# L9963E.net
KiCad netlist of a schematic drawn in Altium Designer
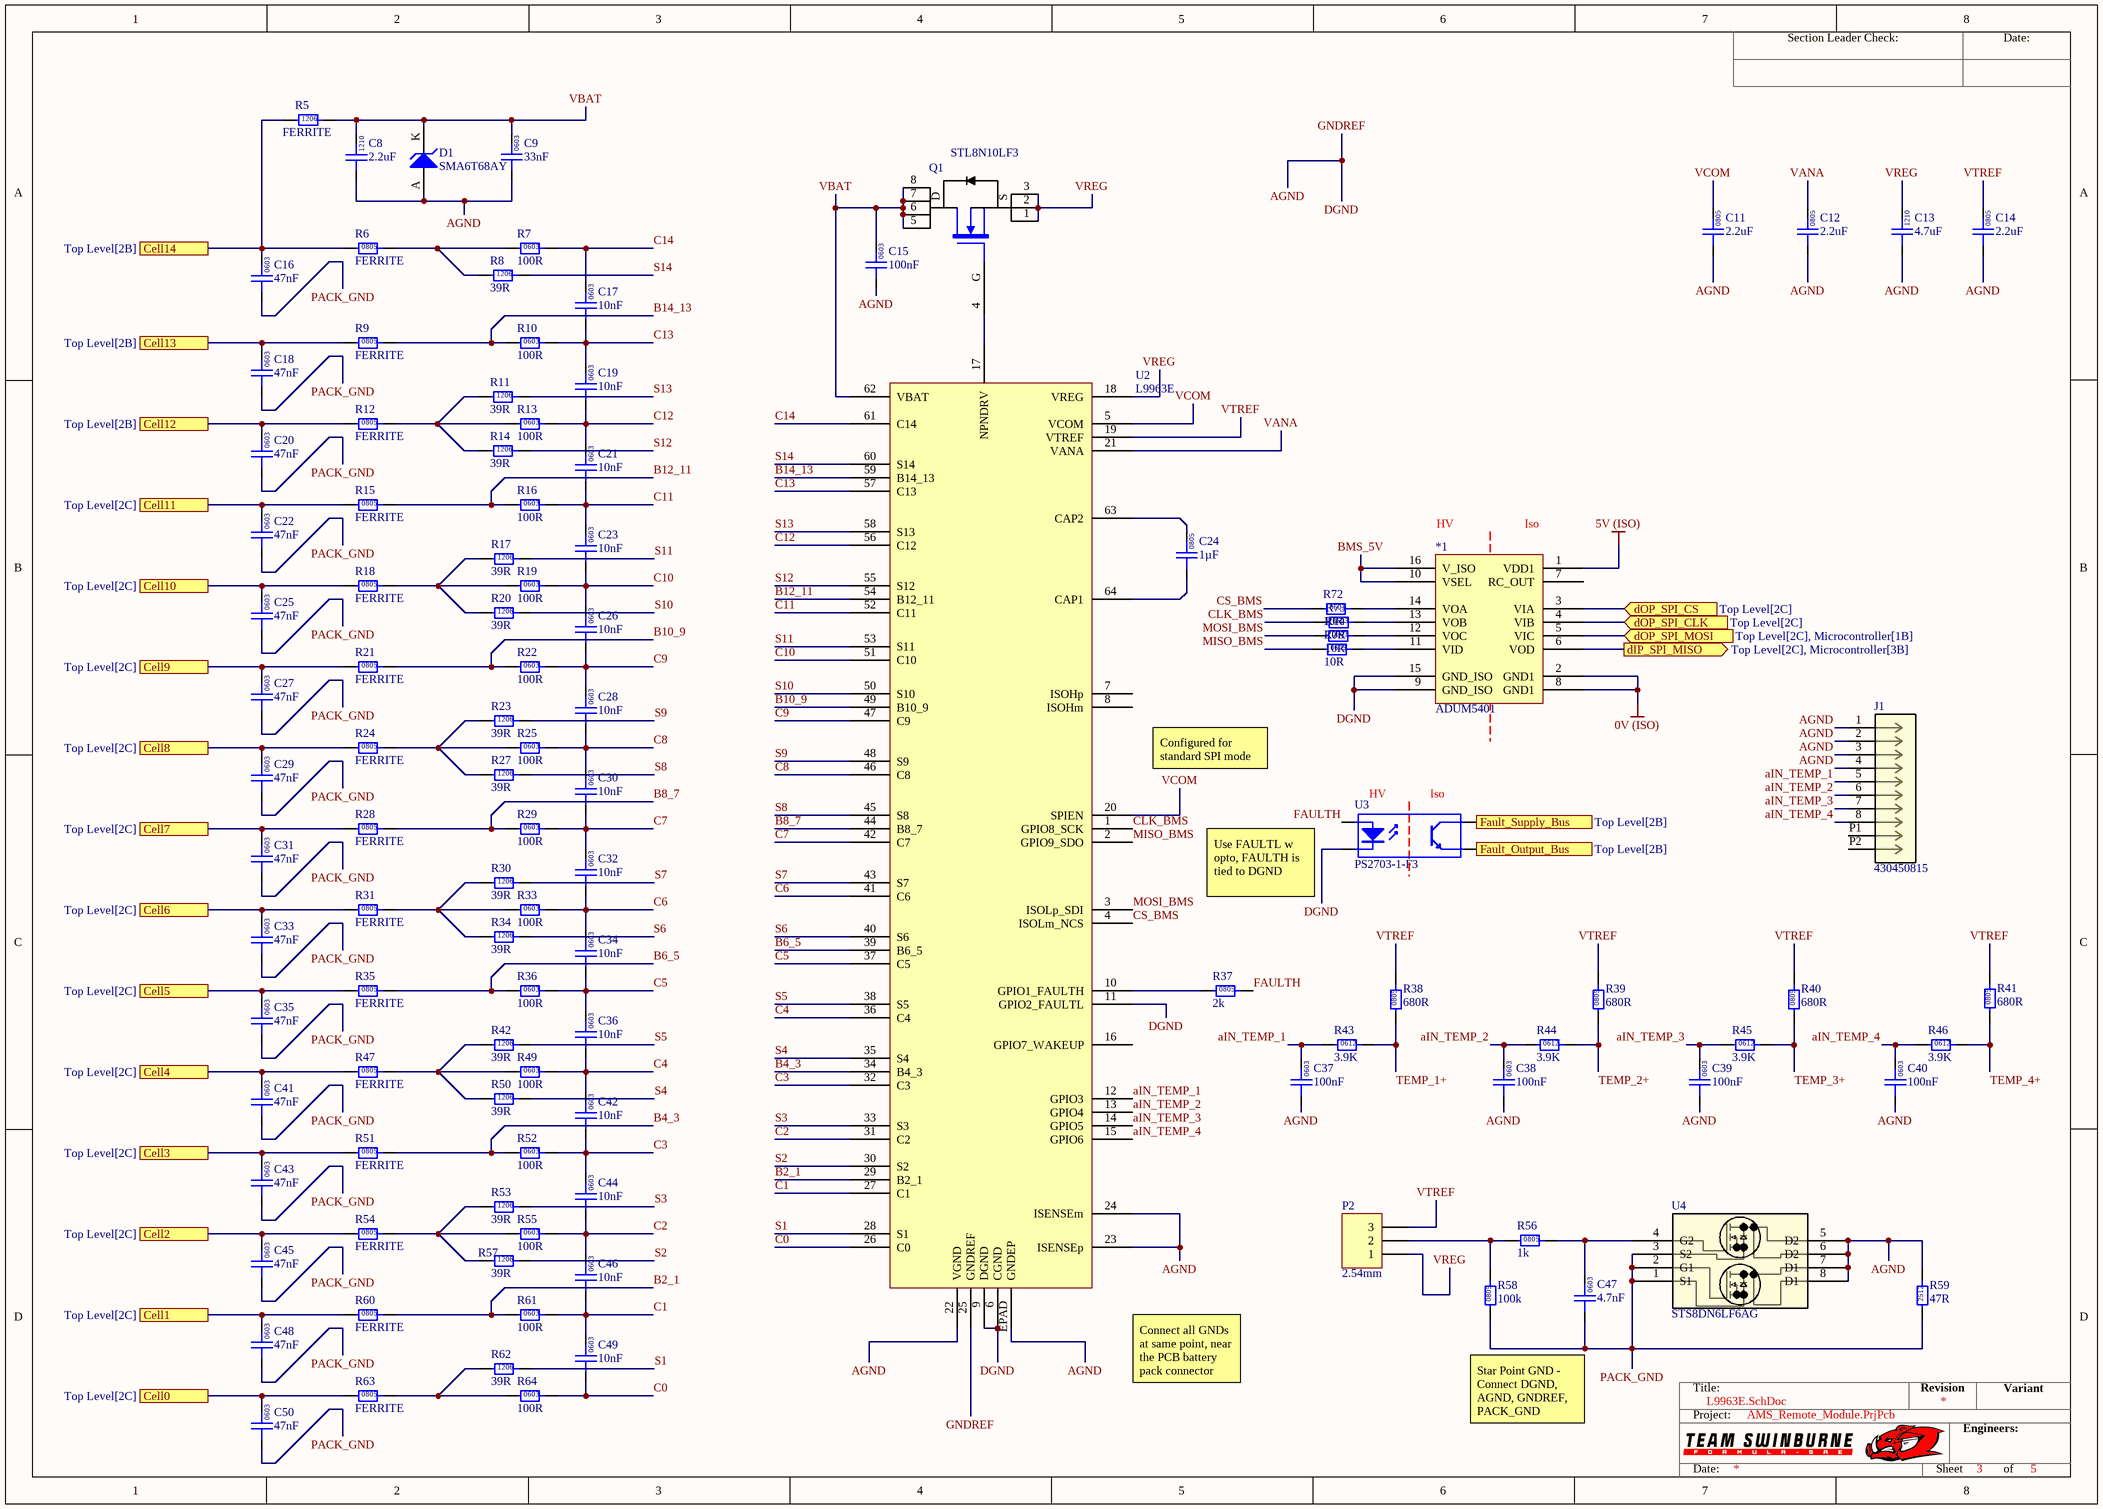
[diagram p0: L9963E.SchDoc]

(export (version "E")
  (design (tool "Eeschema 10.0.6"))
  (components
    (comp (ref "*1")
      (value "ADUM5401")
      (footprint "AD 16-SOIC")
      (description "Quad Channel 2.5kV Digital Isolator with isoPower")
      (fields (field (name "MANUFACTURER") "Analogue Devices"))
      (libsource (lib "ts_standard_library") (part "ADUM5401"))
    )
    (comp (ref "C8")
      (value "2.2uF")
      (footprint "1210")
      (fields
        (field (name "PART NUMBER") "CL32B225KCJSNNE")
        (field (name "MANUFACTURER") "Samsung Electro-Mechanics")
        (field (name "TOLERANCE") "±10%")
      )
      (libsource (lib "ts_standard_library") (part "Capacitor 1210"))
    )
    (comp (ref "C9")
      (value "33nF")
      (footprint "0603")
      (fields
        (field (name "PART NUMBER") "CL10B333KC8WPNC")
        (field (name "MANUFACTURER") "Samsung Electro-Mechanics")
        (field (name "TOLERANCE") "±10%")
      )
      (libsource (lib "ts_standard_library") (part "Capacitor 0603"))
    )
    (comp (ref "C11")
      (value "2.2uF")
      (footprint "0805")
      (fields
        (field (name "PART NUMBER") "GRM21BR71E225KE11L")
        (field (name "MANUFACTURER") "Murata Electronics")
        (field (name "TOLERANCE") "±10%")
      )
      (libsource (lib "ts_standard_library") (part "Capacitor 0805"))
    )
    (comp (ref "C12")
      (value "2.2uF")
      (footprint "0805")
      (fields
        (field (name "PART NUMBER") "GRM21BR71E225KE11L")
        (field (name "MANUFACTURER") "Murata Electronics")
        (field (name "TOLERANCE") "±10%")
      )
      (libsource (lib "ts_standard_library") (part "Capacitor 0805"))
    )
    (comp (ref "C13")
      (value "4.7uF")
      (footprint "1210")
      (fields
        (field (name "PART NUMBER") "C1210X475K101T")
        (field (name "MANUFACTURER") "Holy Stone Enterprise Co., Ltd.")
        (field (name "TOLERANCE") "±10%")
      )
      (libsource (lib "ts_standard_library") (part "Capacitor 1210"))
    )
    (comp (ref "C14")
      (value "2.2uF")
      (footprint "0805")
      (fields
        (field (name "PART NUMBER") "GRM21BR71E225KE11L")
        (field (name "MANUFACTURER") "Murata Electronics")
        (field (name "TOLERANCE") "±10%")
      )
      (libsource (lib "ts_standard_library") (part "Capacitor 0805"))
    )
    (comp (ref "C15")
      (value "100nF")
      (footprint "0603")
      (fields
        (field (name "PART NUMBER") "CL10B104KC8NNNC")
        (field (name "MANUFACTURER") "Samsung Electro-Mechanics")
        (field (name "TOLERANCE") "±10%")
      )
      (libsource (lib "ts_standard_library") (part "Capacitor 0603"))
    )
    (comp (ref "C16")
      (value "47nF")
      (footprint "0603")
      (fields
        (field (name "PART NUMBER") "GCJ188R92A473KA01D")
        (field (name "MANUFACTURER") "Murata Electronics")
        (field (name "TOLERANCE") "±10%")
      )
      (libsource (lib "ts_standard_library") (part "Capacitor 0603"))
    )
    (comp (ref "C17")
      (value "10nF")
      (footprint "0603")
      (fields
        (field (name "PART NUMBER") "GCM188L81H103KA03D")
        (field (name "MANUFACTURER") "muRata")
        (field (name "TOLERANCE") "±10%")
      )
      (libsource (lib "ts_standard_library") (part "Capacitor 0603"))
    )
    (comp (ref "C18")
      (value "47nF")
      (footprint "0603")
      (fields
        (field (name "PART NUMBER") "GCJ188R92A473KA01D")
        (field (name "MANUFACTURER") "Murata Electronics")
        (field (name "TOLERANCE") "±10%")
      )
      (libsource (lib "ts_standard_library") (part "Capacitor 0603"))
    )
    (comp (ref "C19")
      (value "10nF")
      (footprint "0603")
      (fields
        (field (name "PART NUMBER") "GCM188L81H103KA03D")
        (field (name "MANUFACTURER") "muRata")
        (field (name "TOLERANCE") "±10%")
      )
      (libsource (lib "ts_standard_library") (part "Capacitor 0603"))
    )
    (comp (ref "C20")
      (value "47nF")
      (footprint "0603")
      (fields
        (field (name "PART NUMBER") "GCJ188R92A473KA01D")
        (field (name "MANUFACTURER") "Murata Electronics")
        (field (name "TOLERANCE") "±10%")
      )
      (libsource (lib "ts_standard_library") (part "Capacitor 0603"))
    )
    (comp (ref "C21")
      (value "10nF")
      (footprint "0603")
      (fields
        (field (name "PART NUMBER") "GCM188L81H103KA03D")
        (field (name "MANUFACTURER") "muRata")
        (field (name "TOLERANCE") "±10%")
      )
      (libsource (lib "ts_standard_library") (part "Capacitor 0603"))
    )
    (comp (ref "C22")
      (value "47nF")
      (footprint "0603")
      (fields
        (field (name "PART NUMBER") "GCJ188R92A473KA01D")
        (field (name "MANUFACTURER") "Murata Electronics")
        (field (name "TOLERANCE") "±10%")
      )
      (libsource (lib "ts_standard_library") (part "Capacitor 0603"))
    )
    (comp (ref "C23")
      (value "10nF")
      (footprint "0603")
      (fields
        (field (name "PART NUMBER") "GCM188L81H103KA03D")
        (field (name "MANUFACTURER") "muRata")
        (field (name "TOLERANCE") "±10%")
      )
      (libsource (lib "ts_standard_library") (part "Capacitor 0603"))
    )
    (comp (ref "C24")
      (value "1µF")
      (footprint "0805")
      (fields
        (field (name "PART NUMBER") "GCM21BR71H105KA03L")
        (field (name "MANUFACTURER") "muRata")
        (field (name "TOLERANCE") "±10%")
      )
      (libsource (lib "ts_standard_library") (part "Capacitor 0805"))
    )
    (comp (ref "C25")
      (value "47nF")
      (footprint "0603")
      (fields
        (field (name "PART NUMBER") "GCJ188R92A473KA01D")
        (field (name "MANUFACTURER") "Murata Electronics")
        (field (name "TOLERANCE") "±10%")
      )
      (libsource (lib "ts_standard_library") (part "Capacitor 0603"))
    )
    (comp (ref "C26")
      (value "10nF")
      (footprint "0603")
      (fields
        (field (name "PART NUMBER") "GCM188L81H103KA03D")
        (field (name "MANUFACTURER") "muRata")
        (field (name "TOLERANCE") "±10%")
      )
      (libsource (lib "ts_standard_library") (part "Capacitor 0603"))
    )
    (comp (ref "C27")
      (value "47nF")
      (footprint "0603")
      (fields
        (field (name "PART NUMBER") "GCJ188R92A473KA01D")
        (field (name "MANUFACTURER") "Murata Electronics")
        (field (name "TOLERANCE") "±10%")
      )
      (libsource (lib "ts_standard_library") (part "Capacitor 0603"))
    )
    (comp (ref "C28")
      (value "10nF")
      (footprint "0603")
      (fields
        (field (name "PART NUMBER") "GCM188L81H103KA03D")
        (field (name "MANUFACTURER") "muRata")
        (field (name "TOLERANCE") "±10%")
      )
      (libsource (lib "ts_standard_library") (part "Capacitor 0603"))
    )
    (comp (ref "C29")
      (value "47nF")
      (footprint "0603")
      (fields
        (field (name "PART NUMBER") "GCJ188R92A473KA01D")
        (field (name "MANUFACTURER") "Murata Electronics")
        (field (name "TOLERANCE") "±10%")
      )
      (libsource (lib "ts_standard_library") (part "Capacitor 0603"))
    )
    (comp (ref "C30")
      (value "10nF")
      (footprint "0603")
      (fields
        (field (name "PART NUMBER") "GCM188L81H103KA03D")
        (field (name "MANUFACTURER") "muRata")
        (field (name "TOLERANCE") "±10%")
      )
      (libsource (lib "ts_standard_library") (part "Capacitor 0603"))
    )
    (comp (ref "C31")
      (value "47nF")
      (footprint "0603")
      (fields
        (field (name "PART NUMBER") "GCJ188R92A473KA01D")
        (field (name "MANUFACTURER") "Murata Electronics")
        (field (name "TOLERANCE") "±10%")
      )
      (libsource (lib "ts_standard_library") (part "Capacitor 0603"))
    )
    (comp (ref "C32")
      (value "10nF")
      (footprint "0603")
      (fields
        (field (name "PART NUMBER") "GCM188L81H103KA03D")
        (field (name "MANUFACTURER") "muRata")
        (field (name "TOLERANCE") "±10%")
      )
      (libsource (lib "ts_standard_library") (part "Capacitor 0603"))
    )
    (comp (ref "C33")
      (value "47nF")
      (footprint "0603")
      (fields
        (field (name "PART NUMBER") "GCJ188R92A473KA01D")
        (field (name "MANUFACTURER") "Murata Electronics")
        (field (name "TOLERANCE") "±10%")
      )
      (libsource (lib "ts_standard_library") (part "Capacitor 0603"))
    )
    (comp (ref "C34")
      (value "10nF")
      (footprint "0603")
      (fields
        (field (name "PART NUMBER") "GCM188L81H103KA03D")
        (field (name "MANUFACTURER") "muRata")
        (field (name "TOLERANCE") "±10%")
      )
      (libsource (lib "ts_standard_library") (part "Capacitor 0603"))
    )
    (comp (ref "C35")
      (value "47nF")
      (footprint "0603")
      (fields
        (field (name "PART NUMBER") "GCJ188R92A473KA01D")
        (field (name "MANUFACTURER") "Murata Electronics")
        (field (name "TOLERANCE") "±10%")
      )
      (libsource (lib "ts_standard_library") (part "Capacitor 0603"))
    )
    (comp (ref "C36")
      (value "10nF")
      (footprint "0603")
      (fields
        (field (name "PART NUMBER") "GCM188L81H103KA03D")
        (field (name "MANUFACTURER") "muRata")
        (field (name "TOLERANCE") "±10%")
      )
      (libsource (lib "ts_standard_library") (part "Capacitor 0603"))
    )
    (comp (ref "C37")
      (value "100nF")
      (footprint "0603")
      (fields
        (field (name "PART NUMBER") "CL10B104KC8NNNC")
        (field (name "MANUFACTURER") "Samsung Electro-Mechanics")
        (field (name "TOLERANCE") "±10%")
      )
      (libsource (lib "ts_standard_library") (part "Capacitor 0603"))
    )
    (comp (ref "C38")
      (value "100nF")
      (footprint "0603")
      (fields
        (field (name "PART NUMBER") "CL10B104KC8NNNC")
        (field (name "MANUFACTURER") "Samsung Electro-Mechanics")
        (field (name "TOLERANCE") "±10%")
      )
      (libsource (lib "ts_standard_library") (part "Capacitor 0603"))
    )
    (comp (ref "C39")
      (value "100nF")
      (footprint "0603")
      (fields
        (field (name "PART NUMBER") "CL10B104KC8NNNC")
        (field (name "MANUFACTURER") "Samsung Electro-Mechanics")
        (field (name "TOLERANCE") "±10%")
      )
      (libsource (lib "ts_standard_library") (part "Capacitor 0603"))
    )
    (comp (ref "C40")
      (value "100nF")
      (footprint "0603")
      (fields
        (field (name "PART NUMBER") "CL10B104KC8NNNC")
        (field (name "MANUFACTURER") "Samsung Electro-Mechanics")
        (field (name "TOLERANCE") "±10%")
      )
      (libsource (lib "ts_standard_library") (part "Capacitor 0603"))
    )
    (comp (ref "C41")
      (value "47nF")
      (footprint "0603")
      (fields
        (field (name "PART NUMBER") "GCJ188R92A473KA01D")
        (field (name "MANUFACTURER") "Murata Electronics")
        (field (name "TOLERANCE") "±10%")
      )
      (libsource (lib "ts_standard_library") (part "Capacitor 0603"))
    )
    (comp (ref "C42")
      (value "10nF")
      (footprint "0603")
      (fields
        (field (name "PART NUMBER") "GCM188L81H103KA03D")
        (field (name "MANUFACTURER") "muRata")
        (field (name "TOLERANCE") "±10%")
      )
      (libsource (lib "ts_standard_library") (part "Capacitor 0603"))
    )
    (comp (ref "C43")
      (value "47nF")
      (footprint "0603")
      (fields
        (field (name "PART NUMBER") "GCJ188R92A473KA01D")
        (field (name "MANUFACTURER") "Murata Electronics")
        (field (name "TOLERANCE") "±10%")
      )
      (libsource (lib "ts_standard_library") (part "Capacitor 0603"))
    )
    (comp (ref "C44")
      (value "10nF")
      (footprint "0603")
      (fields
        (field (name "PART NUMBER") "GCM188L81H103KA03D")
        (field (name "MANUFACTURER") "muRata")
        (field (name "TOLERANCE") "±10%")
      )
      (libsource (lib "ts_standard_library") (part "Capacitor 0603"))
    )
    (comp (ref "C45")
      (value "47nF")
      (footprint "0603")
      (fields
        (field (name "PART NUMBER") "GCJ188R92A473KA01D")
        (field (name "MANUFACTURER") "Murata Electronics")
        (field (name "TOLERANCE") "±10%")
      )
      (libsource (lib "ts_standard_library") (part "Capacitor 0603"))
    )
    (comp (ref "C46")
      (value "10nF")
      (footprint "0603")
      (fields
        (field (name "PART NUMBER") "GCM188L81H103KA03D")
        (field (name "MANUFACTURER") "muRata")
        (field (name "TOLERANCE") "±10%")
      )
      (libsource (lib "ts_standard_library") (part "Capacitor 0603"))
    )
    (comp (ref "C47")
      (value "4.7nF")
      (footprint "0603")
      (fields
        (field (name "PART NUMBER") "CGA3E2X7R2A472K080AA")
        (field (name "MANUFACTURER") "TDK Corporation")
        (field (name "TOLERANCE") "±10%")
      )
      (libsource (lib "ts_standard_library") (part "Capacitor 0603"))
    )
    (comp (ref "C48")
      (value "47nF")
      (footprint "0603")
      (fields
        (field (name "PART NUMBER") "GCJ188R92A473KA01D")
        (field (name "MANUFACTURER") "Murata Electronics")
        (field (name "TOLERANCE") "±10%")
      )
      (libsource (lib "ts_standard_library") (part "Capacitor 0603"))
    )
    (comp (ref "C49")
      (value "10nF")
      (footprint "0603")
      (fields
        (field (name "PART NUMBER") "GCM188L81H103KA03D")
        (field (name "MANUFACTURER") "muRata")
        (field (name "TOLERANCE") "±10%")
      )
      (libsource (lib "ts_standard_library") (part "Capacitor 0603"))
    )
    (comp (ref "C50")
      (value "47nF")
      (footprint "0603")
      (fields
        (field (name "PART NUMBER") "GCJ188R92A473KA01D")
        (field (name "MANUFACTURER") "Murata Electronics")
        (field (name "TOLERANCE") "±10%")
      )
      (libsource (lib "ts_standard_library") (part "Capacitor 0603"))
    )
    (comp (ref "D1")
      (value "SMA6T68AY")
      (footprint "ST SMB DIODE")
      (fields (field (name "MANUFACTURER") "STMicroelectronics"))
      (libsource (lib "ts_standard_library") (part "Zener Diode"))
    )
    (comp (ref "J1")
      (value "430450815")
      (footprint "430450815")
      (description "No Description Available")
      (fields (field (name "DIGIKEY PART NUMBER") "WM7067DKR-ND") (field (name "CONTACT") "Gold"))
      (libsource (lib "ts_standard_connectors") (part "430450815"))
    )
    (comp (ref "P2")
      (value "2.54mm")
      (footprint "TH 2.54mm Header 1x3")
      (fields (field (name "PART NUMBER") "TH 2.54mm Header 1x3") (field (name "CONTACT") "NA"))
      (libsource (lib "ts_standard_connectors") (part "Header 1x3"))
    )
    (comp (ref "Q1")
      (value "STL8N10LF3")
      (footprint "TRANS_STL60P4LLF6")
      (description "N-Channel 100 V 20A (Tc) 4.3W (Ta), 70W (Tc) Surface Mount PowerFlat™ (5x6)")
      (fields
        (field (name "MANUFACTURER") "STMicroelectronics")
        (field (name "DIGIKEY PART NUMBER") "497-13652-6-ND")
        (field (name "PUBLISHER") "Altium Limited")
      )
      (libsource (lib "ts_standard_library") (part "STL8N10LF3"))
    )
    (comp (ref "R5")
      (value "FERRITE")
      (footprint "1206")
      (fields
        (field (name "PART NUMBER") "BLM31KN102SH1L")
        (field (name "MANUFACTURER") "Murata Electronics")
        (field (name "DIGIKEY PART NUMBER") "490-16520-6-ND")
      )
      (libsource (lib "ts_standard_library") (part "Resistor 1206"))
    )
    (comp (ref "R6")
      (value "FERRITE")
      (footprint "0805")
      (fields (field (name "PART NUMBER") "MPZ2012S102ATD25") (field (name "MANUFACTURER") "TDK"))
      (libsource (lib "ts_standard_library") (part "Resistor 0805"))
    )
    (comp (ref "R7")
      (value "100R")
      (footprint "0603")
      (fields
        (field (name "PART NUMBER") "RC0603FR-0710RL")
        (field (name "MANUFACTURER") "YAGEO")
        (field (name "TOLERANCE") "0.01")
      )
      (libsource (lib "ts_standard_library") (part "Resistor 0603"))
    )
    (comp (ref "R8")
      (value "39R")
      (footprint "1206")
      (fields
        (field (name "PART NUMBER") "CRCW120639R0FKEAHP")
        (field (name "MANUFACTURER") "Vishay Dale")
        (field (name "TOLERANCE") "0.01")
      )
      (libsource (lib "ts_standard_library") (part "Resistor 1206"))
    )
    (comp (ref "R9")
      (value "FERRITE")
      (footprint "0805")
      (fields (field (name "PART NUMBER") "MPZ2012S102ATD25") (field (name "MANUFACTURER") "TDK"))
      (libsource (lib "ts_standard_library") (part "Resistor 0805"))
    )
    (comp (ref "R10")
      (value "100R")
      (footprint "0603")
      (fields
        (field (name "PART NUMBER") "RC0603FR-0710RL")
        (field (name "MANUFACTURER") "YAGEO")
        (field (name "TOLERANCE") "0.01")
      )
      (libsource (lib "ts_standard_library") (part "Resistor 0603"))
    )
    (comp (ref "R11")
      (value "39R")
      (footprint "1206")
      (fields
        (field (name "PART NUMBER") "CRCW120639R0FKEAHP")
        (field (name "MANUFACTURER") "Vishay Dale")
        (field (name "TOLERANCE") "0.01")
      )
      (libsource (lib "ts_standard_library") (part "Resistor 1206"))
    )
    (comp (ref "R12")
      (value "FERRITE")
      (footprint "0805")
      (fields (field (name "PART NUMBER") "MPZ2012S102ATD25") (field (name "MANUFACTURER") "TDK"))
      (libsource (lib "ts_standard_library") (part "Resistor 0805"))
    )
    (comp (ref "R13")
      (value "100R")
      (footprint "0603")
      (fields
        (field (name "PART NUMBER") "RC0603FR-0710RL")
        (field (name "MANUFACTURER") "YAGEO")
        (field (name "TOLERANCE") "0.01")
      )
      (libsource (lib "ts_standard_library") (part "Resistor 0603"))
    )
    (comp (ref "R14")
      (value "39R")
      (footprint "1206")
      (fields
        (field (name "PART NUMBER") "CRCW120639R0FKEAHP")
        (field (name "MANUFACTURER") "Vishay Dale")
        (field (name "TOLERANCE") "0.01")
      )
      (libsource (lib "ts_standard_library") (part "Resistor 1206"))
    )
    (comp (ref "R15")
      (value "FERRITE")
      (footprint "0805")
      (fields (field (name "PART NUMBER") "MPZ2012S102ATD25") (field (name "MANUFACTURER") "TDK"))
      (libsource (lib "ts_standard_library") (part "Resistor 0805"))
    )
    (comp (ref "R16")
      (value "100R")
      (footprint "0603")
      (fields
        (field (name "PART NUMBER") "RC0603FR-0710RL")
        (field (name "MANUFACTURER") "YAGEO")
        (field (name "TOLERANCE") "0.01")
      )
      (libsource (lib "ts_standard_library") (part "Resistor 0603"))
    )
    (comp (ref "R17")
      (value "39R")
      (footprint "1206")
      (fields
        (field (name "PART NUMBER") "CRCW120639R0FKEAHP")
        (field (name "MANUFACTURER") "Vishay Dale")
        (field (name "TOLERANCE") "0.01")
      )
      (libsource (lib "ts_standard_library") (part "Resistor 1206"))
    )
    (comp (ref "R18")
      (value "FERRITE")
      (footprint "0805")
      (fields (field (name "PART NUMBER") "MPZ2012S102ATD25") (field (name "MANUFACTURER") "TDK"))
      (libsource (lib "ts_standard_library") (part "Resistor 0805"))
    )
    (comp (ref "R19")
      (value "100R")
      (footprint "0603")
      (fields
        (field (name "PART NUMBER") "RC0603FR-0710RL")
        (field (name "MANUFACTURER") "YAGEO")
        (field (name "TOLERANCE") "0.01")
      )
      (libsource (lib "ts_standard_library") (part "Resistor 0603"))
    )
    (comp (ref "R20")
      (value "39R")
      (footprint "1206")
      (fields
        (field (name "PART NUMBER") "CRCW120639R0FKEAHP")
        (field (name "MANUFACTURER") "Vishay Dale")
        (field (name "TOLERANCE") "0.01")
      )
      (libsource (lib "ts_standard_library") (part "Resistor 1206"))
    )
    (comp (ref "R21")
      (value "FERRITE")
      (footprint "0805")
      (fields (field (name "PART NUMBER") "MPZ2012S102ATD25") (field (name "MANUFACTURER") "TDK"))
      (libsource (lib "ts_standard_library") (part "Resistor 0805"))
    )
    (comp (ref "R22")
      (value "100R")
      (footprint "0603")
      (fields
        (field (name "PART NUMBER") "RC0603FR-0710RL")
        (field (name "MANUFACTURER") "YAGEO")
        (field (name "TOLERANCE") "0.01")
      )
      (libsource (lib "ts_standard_library") (part "Resistor 0603"))
    )
    (comp (ref "R23")
      (value "39R")
      (footprint "1206")
      (fields
        (field (name "PART NUMBER") "CRCW120639R0FKEAHP")
        (field (name "MANUFACTURER") "Vishay Dale")
        (field (name "TOLERANCE") "0.01")
      )
      (libsource (lib "ts_standard_library") (part "Resistor 1206"))
    )
    (comp (ref "R24")
      (value "FERRITE")
      (footprint "0805")
      (fields (field (name "PART NUMBER") "MPZ2012S102ATD25") (field (name "MANUFACTURER") "TDK"))
      (libsource (lib "ts_standard_library") (part "Resistor 0805"))
    )
    (comp (ref "R25")
      (value "100R")
      (footprint "0603")
      (fields
        (field (name "PART NUMBER") "RC0603FR-0710RL")
        (field (name "MANUFACTURER") "YAGEO")
        (field (name "TOLERANCE") "0.01")
      )
      (libsource (lib "ts_standard_library") (part "Resistor 0603"))
    )
    (comp (ref "R27")
      (value "39R")
      (footprint "1206")
      (fields
        (field (name "PART NUMBER") "CRCW120639R0FKEAHP")
        (field (name "MANUFACTURER") "Vishay Dale")
        (field (name "TOLERANCE") "0.01")
      )
      (libsource (lib "ts_standard_library") (part "Resistor 1206"))
    )
    (comp (ref "R28")
      (value "FERRITE")
      (footprint "0805")
      (fields (field (name "PART NUMBER") "MPZ2012S102ATD25") (field (name "MANUFACTURER") "TDK"))
      (libsource (lib "ts_standard_library") (part "Resistor 0805"))
    )
    (comp (ref "R29")
      (value "100R")
      (footprint "0603")
      (fields
        (field (name "PART NUMBER") "RC0603FR-0710RL")
        (field (name "MANUFACTURER") "YAGEO")
        (field (name "TOLERANCE") "0.01")
      )
      (libsource (lib "ts_standard_library") (part "Resistor 0603"))
    )
    (comp (ref "R30")
      (value "39R")
      (footprint "1206")
      (fields
        (field (name "PART NUMBER") "CRCW120639R0FKEAHP")
        (field (name "MANUFACTURER") "Vishay Dale")
        (field (name "TOLERANCE") "0.01")
      )
      (libsource (lib "ts_standard_library") (part "Resistor 1206"))
    )
    (comp (ref "R31")
      (value "FERRITE")
      (footprint "0805")
      (fields (field (name "PART NUMBER") "MPZ2012S102ATD25") (field (name "MANUFACTURER") "TDK"))
      (libsource (lib "ts_standard_library") (part "Resistor 0805"))
    )
    (comp (ref "R33")
      (value "100R")
      (footprint "0603")
      (fields
        (field (name "PART NUMBER") "RC0603FR-0710RL")
        (field (name "MANUFACTURER") "YAGEO")
        (field (name "TOLERANCE") "0.01")
      )
      (libsource (lib "ts_standard_library") (part "Resistor 0603"))
    )
    (comp (ref "R34")
      (value "39R")
      (footprint "1206")
      (fields
        (field (name "PART NUMBER") "CRCW120639R0FKEAHP")
        (field (name "MANUFACTURER") "Vishay Dale")
        (field (name "TOLERANCE") "0.01")
      )
      (libsource (lib "ts_standard_library") (part "Resistor 1206"))
    )
    (comp (ref "R35")
      (value "FERRITE")
      (footprint "0805")
      (fields (field (name "PART NUMBER") "MPZ2012S102ATD25") (field (name "MANUFACTURER") "TDK"))
      (libsource (lib "ts_standard_library") (part "Resistor 0805"))
    )
    (comp (ref "R36")
      (value "100R")
      (footprint "0603")
      (fields
        (field (name "PART NUMBER") "RC0603FR-0710RL")
        (field (name "MANUFACTURER") "YAGEO")
        (field (name "TOLERANCE") "0.01")
      )
      (libsource (lib "ts_standard_library") (part "Resistor 0603"))
    )
    (comp (ref "R37")
      (value "2k")
      (footprint "0805")
      (fields
        (field (name "PART NUMBER") "RC0805FR072KL")
        (field (name "MANUFACTURER") "YAGEO")
        (field (name "TOLERANCE") "0.01")
      )
      (libsource (lib "ts_standard_library") (part "Resistor 0805"))
    )
    (comp (ref "R38")
      (value "680R")
      (footprint "0805")
      (fields
        (field (name "PART NUMBER") "RCS0805680RFKEA")
        (field (name "MANUFACTURER") "Vishay Dale")
        (field (name "TOLERANCE") "0.01")
      )
      (libsource (lib "ts_standard_library") (part "Resistor 0805"))
    )
    (comp (ref "R39")
      (value "680R")
      (footprint "0805")
      (fields
        (field (name "PART NUMBER") "RCS0805680RFKEA")
        (field (name "MANUFACTURER") "Vishay Dale")
        (field (name "TOLERANCE") "0.01")
      )
      (libsource (lib "ts_standard_library") (part "Resistor 0805"))
    )
    (comp (ref "R40")
      (value "680R")
      (footprint "0805")
      (fields
        (field (name "PART NUMBER") "RCS0805680RFKEA")
        (field (name "MANUFACTURER") "Vishay Dale")
        (field (name "TOLERANCE") "0.01")
      )
      (libsource (lib "ts_standard_library") (part "Resistor 0805"))
    )
    (comp (ref "R41")
      (value "680R")
      (footprint "0805")
      (fields
        (field (name "PART NUMBER") "RCS0805680RFKEA")
        (field (name "MANUFACTURER") "Vishay Dale")
        (field (name "TOLERANCE") "0.01")
      )
      (libsource (lib "ts_standard_library") (part "Resistor 0805"))
    )
    (comp (ref "R42")
      (value "39R")
      (footprint "1206")
      (fields
        (field (name "PART NUMBER") "CRCW120639R0FKEAHP")
        (field (name "MANUFACTURER") "Vishay Dale")
        (field (name "TOLERANCE") "0.01")
      )
      (libsource (lib "ts_standard_library") (part "Resistor 1206"))
    )
    (comp (ref "R43")
      (value "3.9K")
      (footprint "0612")
      (fields
        (field (name "PART NUMBER") "3430B2F3K9TDF")
        (field (name "MANUFACTURER") "TE Connectivity Passive Product")
        (field (name "TOLERANCE") "0.01")
      )
      (libsource (lib "ts_standard_library") (part "Resistor 0612"))
    )
    (comp (ref "R44")
      (value "3.9K")
      (footprint "0612")
      (fields
        (field (name "PART NUMBER") "3430B2F3K9TDF")
        (field (name "MANUFACTURER") "TE Connectivity Passive Product")
        (field (name "TOLERANCE") "0.01")
      )
      (libsource (lib "ts_standard_library") (part "Resistor 0612"))
    )
    (comp (ref "R45")
      (value "3.9K")
      (footprint "0612")
      (fields
        (field (name "PART NUMBER") "3430B2F3K9TDF")
        (field (name "MANUFACTURER") "TE Connectivity Passive Product")
        (field (name "TOLERANCE") "0.01")
      )
      (libsource (lib "ts_standard_library") (part "Resistor 0612"))
    )
    (comp (ref "R46")
      (value "3.9K")
      (footprint "0612")
      (fields
        (field (name "PART NUMBER") "3430B2F3K9TDF")
        (field (name "MANUFACTURER") "TE Connectivity Passive Product")
        (field (name "TOLERANCE") "0.01")
      )
      (libsource (lib "ts_standard_library") (part "Resistor 0612"))
    )
    (comp (ref "R47")
      (value "FERRITE")
      (footprint "0805")
      (fields (field (name "PART NUMBER") "MPZ2012S102ATD25") (field (name "MANUFACTURER") "TDK"))
      (libsource (lib "ts_standard_library") (part "Resistor 0805"))
    )
    (comp (ref "R49")
      (value "100R")
      (footprint "0603")
      (fields
        (field (name "PART NUMBER") "RC0603FR-0710RL")
        (field (name "MANUFACTURER") "YAGEO")
        (field (name "TOLERANCE") "0.01")
      )
      (libsource (lib "ts_standard_library") (part "Resistor 0603"))
    )
    (comp (ref "R50")
      (value "39R")
      (footprint "1206")
      (fields
        (field (name "PART NUMBER") "CRCW120639R0FKEAHP")
        (field (name "MANUFACTURER") "Vishay Dale")
        (field (name "TOLERANCE") "0.01")
      )
      (libsource (lib "ts_standard_library") (part "Resistor 1206"))
    )
    (comp (ref "R51")
      (value "FERRITE")
      (footprint "0805")
      (fields (field (name "PART NUMBER") "MPZ2012S102ATD25") (field (name "MANUFACTURER") "TDK"))
      (libsource (lib "ts_standard_library") (part "Resistor 0805"))
    )
    (comp (ref "R52")
      (value "100R")
      (footprint "0603")
      (fields
        (field (name "PART NUMBER") "RC0603FR-0710RL")
        (field (name "MANUFACTURER") "YAGEO")
        (field (name "TOLERANCE") "0.01")
      )
      (libsource (lib "ts_standard_library") (part "Resistor 0603"))
    )
    (comp (ref "R53")
      (value "39R")
      (footprint "1206")
      (fields
        (field (name "PART NUMBER") "CRCW120639R0FKEAHP")
        (field (name "MANUFACTURER") "Vishay Dale")
        (field (name "TOLERANCE") "0.01")
      )
      (libsource (lib "ts_standard_library") (part "Resistor 1206"))
    )
    (comp (ref "R54")
      (value "FERRITE")
      (footprint "0805")
      (fields (field (name "PART NUMBER") "MPZ2012S102ATD25") (field (name "MANUFACTURER") "TDK"))
      (libsource (lib "ts_standard_library") (part "Resistor 0805"))
    )
    (comp (ref "R55")
      (value "100R")
      (footprint "0603")
      (fields
        (field (name "PART NUMBER") "RC0603FR-0710RL")
        (field (name "MANUFACTURER") "YAGEO")
        (field (name "TOLERANCE") "0.01")
      )
      (libsource (lib "ts_standard_library") (part "Resistor 0603"))
    )
    (comp (ref "R56")
      (value "1k")
      (footprint "0805")
      (fields
        (field (name "PART NUMBER") "RC0805FR071KL")
        (field (name "MANUFACTURER") "YAGEO")
        (field (name "TOLERANCE") "0.01")
      )
      (libsource (lib "ts_standard_library") (part "Resistor 0805"))
    )
    (comp (ref "R57")
      (value "39R")
      (footprint "1206")
      (fields
        (field (name "PART NUMBER") "CRCW120639R0FKEAHP")
        (field (name "MANUFACTURER") "Vishay Dale")
        (field (name "TOLERANCE") "0.01")
      )
      (libsource (lib "ts_standard_library") (part "Resistor 1206"))
    )
    (comp (ref "R58")
      (value "100k")
      (footprint "0805")
      (fields
        (field (name "PART NUMBER") "RC0805FR07100KL")
        (field (name "MANUFACTURER") "YAGEO")
        (field (name "TOLERANCE") "0.01")
      )
      (libsource (lib "ts_standard_library") (part "Resistor 0805"))
    )
    (comp (ref "R59")
      (value "47R")
      (footprint "2512")
      (fields
        (field (name "PART NUMBER") "CRCW251247R0FKEG")
        (field (name "MANUFACTURER") "Vishay Dale")
        (field (name "TOLERANCE") "0.01")
      )
      (libsource (lib "ts_standard_library") (part "Resistor 2512"))
    )
    (comp (ref "R60")
      (value "FERRITE")
      (footprint "0805")
      (fields (field (name "PART NUMBER") "MPZ2012S102ATD25") (field (name "MANUFACTURER") "TDK"))
      (libsource (lib "ts_standard_library") (part "Resistor 0805"))
    )
    (comp (ref "R61")
      (value "100R")
      (footprint "0603")
      (fields
        (field (name "PART NUMBER") "RC0603FR-0710RL")
        (field (name "MANUFACTURER") "YAGEO")
        (field (name "TOLERANCE") "0.01")
      )
      (libsource (lib "ts_standard_library") (part "Resistor 0603"))
    )
    (comp (ref "R62")
      (value "39R")
      (footprint "1206")
      (fields
        (field (name "PART NUMBER") "CRCW120639R0FKEAHP")
        (field (name "MANUFACTURER") "Vishay Dale")
        (field (name "TOLERANCE") "0.01")
      )
      (libsource (lib "ts_standard_library") (part "Resistor 1206"))
    )
    (comp (ref "R63")
      (value "FERRITE")
      (footprint "0805")
      (fields (field (name "PART NUMBER") "MPZ2012S102ATD25") (field (name "MANUFACTURER") "TDK"))
      (libsource (lib "ts_standard_library") (part "Resistor 0805"))
    )
    (comp (ref "R64")
      (value "100R")
      (footprint "0603")
      (fields
        (field (name "PART NUMBER") "RC0603FR-0710RL")
        (field (name "MANUFACTURER") "YAGEO")
        (field (name "TOLERANCE") "0.01")
      )
      (libsource (lib "ts_standard_library") (part "Resistor 0603"))
    )
    (comp (ref "R72")
      (value "10R")
      (footprint "0603")
      (fields
        (field (name "PART NUMBER") "RC0603FR-0710RL")
        (field (name "MANUFACTURER") "YAGEO")
        (field (name "TOLERANCE") "0.01")
      )
      (libsource (lib "ts_standard_library") (part "Resistor 0603"))
    )
    (comp (ref "R73")
      (value "10R")
      (footprint "0603")
      (fields
        (field (name "PART NUMBER") "RC0603FR-0710RL")
        (field (name "MANUFACTURER") "YAGEO")
        (field (name "TOLERANCE") "0.01")
      )
      (libsource (lib "ts_standard_library") (part "Resistor 0603"))
    )
    (comp (ref "R74")
      (value "10R")
      (footprint "0603")
      (fields
        (field (name "PART NUMBER") "RC0603FR-0710RL")
        (field (name "MANUFACTURER") "YAGEO")
        (field (name "TOLERANCE") "0.01")
      )
      (libsource (lib "ts_standard_library") (part "Resistor 0603"))
    )
    (comp (ref "R75")
      (value "10R")
      (footprint "0603")
      (fields
        (field (name "PART NUMBER") "RC0603FR-0710RL")
        (field (name "MANUFACTURER") "YAGEO")
        (field (name "TOLERANCE") "0.01")
      )
      (libsource (lib "ts_standard_library") (part "Resistor 0603"))
    )
    (comp (ref "U2")
      (value "L9963E")
      (footprint "TQFP64_L9963E_STM")
      (description "AUTOMOTIVE CHIP FOR BATTERY MANA")
      (fields (field (name "MANUFACTURER") "ST Microelectronics"))
      (libsource (lib "ts_standard_library") (part "L9963E"))
    )
    (comp (ref "U3")
      (value "PS2703-1-F3")
      (footprint "4-SOP")
      (description "OPTOISOLATOR 3.75KV TRANS 4SMD")
      (fields
        (field (name "MANUFACTURER") "Renesas Electronics Corporation")
        (field (name "DIGIKEY PART NUMBER") "559-1155-6-ND")
      )
      (libsource (lib "ts_standard_library") (part "PS2703-1-F3-A"))
    )
    (comp (ref "U4")
      (value "STS8DN6LF6AG")
      (footprint "SO-8_STM-M")
      (description "Mosfet Array 60V 8A (Ta) 3.2W Surface Mount 8-SO")
      (fields
        (field (name "MANUFACTURER") "STMicroelectronics")
        (field (name "DIGIKEY PART NUMBER") "497-17309-6-ND")
      )
      (libsource (lib "ts_standard_library") (part "STS8DN6LF6AG"))
    )
  )
  (nets
    (net (code "1") (name "/AGND") (class "Default")
      (node (ref "*1") (pin "15") (pinfunction "GND_ISO_15") (pintype "passive"))
      (node (ref "*1") (pin "9") (pinfunction "GND_ISO_9") (pintype "passive"))
      (node (ref "C11") (pin "1") (pinfunction "1_1") (pintype "passive"))
      (node (ref "C12") (pin "1") (pinfunction "1_1") (pintype "passive"))
      (node (ref "C13") (pin "1") (pinfunction "1_1") (pintype "passive"))
      (node (ref "C14") (pin "1") (pinfunction "1_1") (pintype "passive"))
      (node (ref "C15") (pin "1") (pinfunction "1_1") (pintype "passive"))
      (node (ref "C37") (pin "1") (pinfunction "1_1") (pintype "passive"))
      (node (ref "C38") (pin "1") (pinfunction "1_1") (pintype "passive"))
      (node (ref "C39") (pin "1") (pinfunction "1_1") (pintype "passive"))
      (node (ref "C40") (pin "1") (pinfunction "1_1") (pintype "passive"))
      (node (ref "C8") (pin "1") (pinfunction "1_1") (pintype "passive"))
      (node (ref "C9") (pin "1") (pinfunction "1_1") (pintype "passive"))
      (node (ref "D1") (pin "A") (pinfunction "A_A") (pintype "passive"))
      (node (ref "J1") (pin "1") (pinfunction "1_1") (pintype "passive"))
      (node (ref "J1") (pin "2") (pinfunction "2_2") (pintype "passive"))
      (node (ref "J1") (pin "3") (pinfunction "3_3") (pintype "passive"))
      (node (ref "J1") (pin "4") (pinfunction "4_4") (pintype "passive"))
      (node (ref "R59") (pin "2") (pinfunction "2_2") (pintype "passive"))
      (node (ref "U2") (pin "11") (pinfunction "GPIO2_FAULTL_11") (pintype "passive"))
      (node (ref "U2") (pin "22") (pinfunction "VGND_22") (pintype "passive"))
      (node (ref "U2") (pin "23") (pinfunction "ISENSEp_23") (pintype "passive"))
      (node (ref "U2") (pin "24") (pinfunction "ISENSEm_24") (pintype "passive"))
      (node (ref "U2") (pin "25") (pinfunction "GNDREF_25") (pintype "passive"))
      (node (ref "U2") (pin "6") (pinfunction "CGND_6") (pintype "passive"))
      (node (ref "U2") (pin "9") (pinfunction "DGND_9") (pintype "passive"))
      (node (ref "U2") (pin "EPAD") (pinfunction "GNDEP_EPAD") (pintype "passive"))
      (node (ref "U3") (pin "2") (pinfunction "K_2") (pintype "passive"))
      (node (ref "U4") (pin "5") (pinfunction "D2_5") (pintype "passive"))
      (node (ref "U4") (pin "6") (pinfunction "D2_6") (pintype "passive"))
      (node (ref "U4") (pin "7") (pinfunction "D1_7") (pintype "passive"))
      (node (ref "U4") (pin "8") (pinfunction "D1_8") (pintype "passive"))
    )
    (net (code "2") (name "/B2_1") (class "Default")
      (node (ref "R60") (pin "2") (pinfunction "2_2") (pintype "passive"))
      (node (ref "R61") (pin "1") (pinfunction "1_1") (pintype "passive"))
      (node (ref "U2") (pin "29") (pinfunction "B2_1_29") (pintype "passive"))
    )
    (net (code "3") (name "/B4_3") (class "Default")
      (node (ref "R51") (pin "2") (pinfunction "2_2") (pintype "passive"))
      (node (ref "R52") (pin "1") (pinfunction "1_1") (pintype "passive"))
      (node (ref "U2") (pin "34") (pinfunction "B4_3_34") (pintype "passive"))
    )
    (net (code "4") (name "/B6_5") (class "Default")
      (node (ref "R35") (pin "2") (pinfunction "2_2") (pintype "passive"))
      (node (ref "R36") (pin "1") (pinfunction "1_1") (pintype "passive"))
      (node (ref "U2") (pin "39") (pinfunction "B6_5_39") (pintype "passive"))
    )
    (net (code "5") (name "/B8_7") (class "Default")
      (node (ref "R28") (pin "2") (pinfunction "2_2") (pintype "passive"))
      (node (ref "R29") (pin "1") (pinfunction "1_1") (pintype "passive"))
      (node (ref "U2") (pin "44") (pinfunction "B8_7_44") (pintype "passive"))
    )
    (net (code "6") (name "/B10_9") (class "Default")
      (node (ref "R21") (pin "2") (pinfunction "2_2") (pintype "passive"))
      (node (ref "R22") (pin "1") (pinfunction "1_1") (pintype "passive"))
      (node (ref "U2") (pin "49") (pinfunction "B10_9_49") (pintype "passive"))
    )
    (net (code "7") (name "/B12_11") (class "Default")
      (node (ref "R15") (pin "2") (pinfunction "2_2") (pintype "passive"))
      (node (ref "R16") (pin "1") (pinfunction "1_1") (pintype "passive"))
      (node (ref "U2") (pin "54") (pinfunction "B12_11_54") (pintype "passive"))
    )
    (net (code "8") (name "/B14_13") (class "Default")
      (node (ref "R10") (pin "1") (pinfunction "1_1") (pintype "passive"))
      (node (ref "R9") (pin "2") (pinfunction "2_2") (pintype "passive"))
      (node (ref "U2") (pin "59") (pinfunction "B14_13_59") (pintype "passive"))
    )
    (net (code "9") (name "/BMS_5V") (class "Default")
      (node (ref "*1") (pin "10") (pinfunction "VSEL_10") (pintype "passive"))
      (node (ref "*1") (pin "16") (pinfunction "V_ISO_16") (pintype "passive"))
    )
    (net (code "10") (name "/C0") (class "Default")
      (node (ref "C49") (pin "1") (pinfunction "1_1") (pintype "passive"))
      (node (ref "R64") (pin "2") (pinfunction "2_2") (pintype "passive"))
      (node (ref "U2") (pin "26") (pinfunction "C0_26") (pintype "passive"))
    )
    (net (code "11") (name "/C1") (class "Default")
      (node (ref "C46") (pin "1") (pinfunction "1_1") (pintype "passive"))
      (node (ref "C49") (pin "2") (pinfunction "2_2") (pintype "passive"))
      (node (ref "R61") (pin "2") (pinfunction "2_2") (pintype "passive"))
      (node (ref "U2") (pin "27") (pinfunction "C1_27") (pintype "passive"))
    )
    (net (code "12") (name "/C2") (class "Default")
      (node (ref "C44") (pin "1") (pinfunction "1_1") (pintype "passive"))
      (node (ref "C46") (pin "2") (pinfunction "2_2") (pintype "passive"))
      (node (ref "R55") (pin "2") (pinfunction "2_2") (pintype "passive"))
      (node (ref "U2") (pin "31") (pinfunction "C2_31") (pintype "passive"))
    )
    (net (code "13") (name "/C3") (class "Default")
      (node (ref "C42") (pin "1") (pinfunction "1_1") (pintype "passive"))
      (node (ref "C44") (pin "2") (pinfunction "2_2") (pintype "passive"))
      (node (ref "R52") (pin "2") (pinfunction "2_2") (pintype "passive"))
      (node (ref "U2") (pin "32") (pinfunction "C3_32") (pintype "passive"))
    )
    (net (code "14") (name "/C4") (class "Default")
      (node (ref "C36") (pin "1") (pinfunction "1_1") (pintype "passive"))
      (node (ref "C42") (pin "2") (pinfunction "2_2") (pintype "passive"))
      (node (ref "R49") (pin "2") (pinfunction "2_2") (pintype "passive"))
      (node (ref "U2") (pin "36") (pinfunction "C4_36") (pintype "passive"))
    )
    (net (code "15") (name "/C5") (class "Default")
      (node (ref "C34") (pin "1") (pinfunction "1_1") (pintype "passive"))
      (node (ref "C36") (pin "2") (pinfunction "2_2") (pintype "passive"))
      (node (ref "R36") (pin "2") (pinfunction "2_2") (pintype "passive"))
      (node (ref "U2") (pin "37") (pinfunction "C5_37") (pintype "passive"))
    )
    (net (code "16") (name "/C6") (class "Default")
      (node (ref "C32") (pin "1") (pinfunction "1_1") (pintype "passive"))
      (node (ref "C34") (pin "2") (pinfunction "2_2") (pintype "passive"))
      (node (ref "R33") (pin "2") (pinfunction "2_2") (pintype "passive"))
      (node (ref "U2") (pin "41") (pinfunction "C6_41") (pintype "passive"))
    )
    (net (code "17") (name "/C7") (class "Default")
      (node (ref "C30") (pin "1") (pinfunction "1_1") (pintype "passive"))
      (node (ref "C32") (pin "2") (pinfunction "2_2") (pintype "passive"))
      (node (ref "R29") (pin "2") (pinfunction "2_2") (pintype "passive"))
      (node (ref "U2") (pin "42") (pinfunction "C7_42") (pintype "passive"))
    )
    (net (code "18") (name "/C8") (class "Default")
      (node (ref "C28") (pin "1") (pinfunction "1_1") (pintype "passive"))
      (node (ref "C30") (pin "2") (pinfunction "2_2") (pintype "passive"))
      (node (ref "R25") (pin "2") (pinfunction "2_2") (pintype "passive"))
      (node (ref "U2") (pin "46") (pinfunction "C8_46") (pintype "passive"))
    )
    (net (code "19") (name "/C9") (class "Default")
      (node (ref "C26") (pin "1") (pinfunction "1_1") (pintype "passive"))
      (node (ref "C28") (pin "2") (pinfunction "2_2") (pintype "passive"))
      (node (ref "R22") (pin "2") (pinfunction "2_2") (pintype "passive"))
      (node (ref "U2") (pin "47") (pinfunction "C9_47") (pintype "passive"))
    )
    (net (code "20") (name "/C10") (class "Default")
      (node (ref "C23") (pin "1") (pinfunction "1_1") (pintype "passive"))
      (node (ref "C26") (pin "2") (pinfunction "2_2") (pintype "passive"))
      (node (ref "R19") (pin "2") (pinfunction "2_2") (pintype "passive"))
      (node (ref "U2") (pin "51") (pinfunction "C10_51") (pintype "passive"))
    )
    (net (code "21") (name "/C11") (class "Default")
      (node (ref "C21") (pin "1") (pinfunction "1_1") (pintype "passive"))
      (node (ref "C23") (pin "2") (pinfunction "2_2") (pintype "passive"))
      (node (ref "R16") (pin "2") (pinfunction "2_2") (pintype "passive"))
      (node (ref "U2") (pin "52") (pinfunction "C11_52") (pintype "passive"))
    )
    (net (code "22") (name "/C12") (class "Default")
      (node (ref "C19") (pin "1") (pinfunction "1_1") (pintype "passive"))
      (node (ref "C21") (pin "2") (pinfunction "2_2") (pintype "passive"))
      (node (ref "R13") (pin "2") (pinfunction "2_2") (pintype "passive"))
      (node (ref "U2") (pin "56") (pinfunction "C12_56") (pintype "passive"))
    )
    (net (code "23") (name "/C13") (class "Default")
      (node (ref "C17") (pin "1") (pinfunction "1_1") (pintype "passive"))
      (node (ref "C19") (pin "2") (pinfunction "2_2") (pintype "passive"))
      (node (ref "R10") (pin "2") (pinfunction "2_2") (pintype "passive"))
      (node (ref "U2") (pin "57") (pinfunction "C13_57") (pintype "passive"))
    )
    (net (code "24") (name "/C14") (class "Default")
      (node (ref "C17") (pin "2") (pinfunction "2_2") (pintype "passive"))
      (node (ref "R7") (pin "2") (pinfunction "2_2") (pintype "passive"))
      (node (ref "U2") (pin "61") (pinfunction "C14_61") (pintype "passive"))
    )
    (net (code "25") (name "/CLK_BMS") (class "Default")
      (node (ref "R73") (pin "1") (pinfunction "1_1") (pintype "passive"))
      (node (ref "U2") (pin "1") (pinfunction "GPIO8_SCK_1") (pintype "passive"))
    )
    (net (code "26") (name "/CS_BMS") (class "Default")
      (node (ref "R72") (pin "1") (pinfunction "1_1") (pintype "passive"))
      (node (ref "U2") (pin "4") (pinfunction "ISOLm_NCS_4") (pintype "passive"))
    )
    (net (code "27") (name "/Cell0") (class "Default")
      (node (ref "C50") (pin "2") (pinfunction "2_2") (pintype "passive"))
      (node (ref "R63") (pin "1") (pinfunction "1_1") (pintype "passive"))
    )
    (net (code "28") (name "/Cell1") (class "Default")
      (node (ref "C48") (pin "2") (pinfunction "2_2") (pintype "passive"))
      (node (ref "R60") (pin "1") (pinfunction "1_1") (pintype "passive"))
    )
    (net (code "29") (name "/Cell2") (class "Default")
      (node (ref "C45") (pin "2") (pinfunction "2_2") (pintype "passive"))
      (node (ref "R54") (pin "1") (pinfunction "1_1") (pintype "passive"))
    )
    (net (code "30") (name "/Cell3") (class "Default")
      (node (ref "C43") (pin "2") (pinfunction "2_2") (pintype "passive"))
      (node (ref "R51") (pin "1") (pinfunction "1_1") (pintype "passive"))
    )
    (net (code "31") (name "/Cell4") (class "Default")
      (node (ref "C41") (pin "2") (pinfunction "2_2") (pintype "passive"))
      (node (ref "R47") (pin "1") (pinfunction "1_1") (pintype "passive"))
    )
    (net (code "32") (name "/Cell5") (class "Default")
      (node (ref "C35") (pin "2") (pinfunction "2_2") (pintype "passive"))
      (node (ref "R35") (pin "1") (pinfunction "1_1") (pintype "passive"))
    )
    (net (code "33") (name "/Cell6") (class "Default")
      (node (ref "C33") (pin "2") (pinfunction "2_2") (pintype "passive"))
      (node (ref "R31") (pin "1") (pinfunction "1_1") (pintype "passive"))
    )
    (net (code "34") (name "/Cell7") (class "Default")
      (node (ref "C31") (pin "2") (pinfunction "2_2") (pintype "passive"))
      (node (ref "R28") (pin "1") (pinfunction "1_1") (pintype "passive"))
    )
    (net (code "35") (name "/Cell8") (class "Default")
      (node (ref "C29") (pin "2") (pinfunction "2_2") (pintype "passive"))
      (node (ref "R24") (pin "1") (pinfunction "1_1") (pintype "passive"))
    )
    (net (code "36") (name "/Cell9") (class "Default")
      (node (ref "C27") (pin "2") (pinfunction "2_2") (pintype "passive"))
      (node (ref "R21") (pin "1") (pinfunction "1_1") (pintype "passive"))
    )
    (net (code "37") (name "/Cell10") (class "Default")
      (node (ref "C25") (pin "2") (pinfunction "2_2") (pintype "passive"))
      (node (ref "R18") (pin "1") (pinfunction "1_1") (pintype "passive"))
    )
    (net (code "38") (name "/Cell11") (class "Default")
      (node (ref "C22") (pin "2") (pinfunction "2_2") (pintype "passive"))
      (node (ref "R15") (pin "1") (pinfunction "1_1") (pintype "passive"))
    )
    (net (code "39") (name "/Cell12") (class "Default")
      (node (ref "C20") (pin "2") (pinfunction "2_2") (pintype "passive"))
      (node (ref "R12") (pin "1") (pinfunction "1_1") (pintype "passive"))
    )
    (net (code "40") (name "/Cell13") (class "Default")
      (node (ref "C18") (pin "2") (pinfunction "2_2") (pintype "passive"))
      (node (ref "R9") (pin "1") (pinfunction "1_1") (pintype "passive"))
    )
    (net (code "41") (name "/Cell14") (class "Default")
      (node (ref "C16") (pin "2") (pinfunction "2_2") (pintype "passive"))
      (node (ref "R5") (pin "1") (pinfunction "1_1") (pintype "passive"))
      (node (ref "R6") (pin "1") (pinfunction "1_1") (pintype "passive"))
    )
    (net (code "42") (name "/FAULTH") (class "Default")
      (node (ref "R37") (pin "2") (pinfunction "2_2") (pintype "passive"))
      (node (ref "U3") (pin "1") (pinfunction "A_1") (pintype "passive"))
    )
    (net (code "43") (name "/Fault_Output_Bus") (class "Default")
      (node (ref "U3") (pin "3") (pinfunction "E_3") (pintype "passive"))
    )
    (net (code "44") (name "/Fault_Supply_Bus") (class "Default")
      (node (ref "U3") (pin "4") (pinfunction "C_4") (pintype "passive"))
    )
    (net (code "45") (name "/MISO_BMS") (class "Default")
      (node (ref "R75") (pin "1") (pinfunction "1_1") (pintype "passive"))
      (node (ref "U2") (pin "2") (pinfunction "GPIO9_SDO_2") (pintype "passive"))
    )
    (net (code "46") (name "/MOSI_BMS") (class "Default")
      (node (ref "R74") (pin "1") (pinfunction "1_1") (pintype "passive"))
      (node (ref "U2") (pin "3") (pinfunction "ISOLp_SDI_3") (pintype "passive"))
    )
    (net (code "47") (name "/PACK_GND") (class "Default")
      (node (ref "C16") (pin "1") (pinfunction "1_1") (pintype "passive"))
      (node (ref "C18") (pin "1") (pinfunction "1_1") (pintype "passive"))
      (node (ref "C20") (pin "1") (pinfunction "1_1") (pintype "passive"))
      (node (ref "C22") (pin "1") (pinfunction "1_1") (pintype "passive"))
      (node (ref "C25") (pin "1") (pinfunction "1_1") (pintype "passive"))
      (node (ref "C27") (pin "1") (pinfunction "1_1") (pintype "passive"))
      (node (ref "C29") (pin "1") (pinfunction "1_1") (pintype "passive"))
      (node (ref "C31") (pin "1") (pinfunction "1_1") (pintype "passive"))
      (node (ref "C33") (pin "1") (pinfunction "1_1") (pintype "passive"))
      (node (ref "C35") (pin "1") (pinfunction "1_1") (pintype "passive"))
      (node (ref "C41") (pin "1") (pinfunction "1_1") (pintype "passive"))
      (node (ref "C43") (pin "1") (pinfunction "1_1") (pintype "passive"))
      (node (ref "C45") (pin "1") (pinfunction "1_1") (pintype "passive"))
      (node (ref "C47") (pin "1") (pinfunction "1_1") (pintype "passive"))
      (node (ref "C48") (pin "1") (pinfunction "1_1") (pintype "passive"))
      (node (ref "C50") (pin "1") (pinfunction "1_1") (pintype "passive"))
      (node (ref "R58") (pin "1") (pinfunction "1_1") (pintype "passive"))
      (node (ref "R59") (pin "1") (pinfunction "1_1") (pintype "passive"))
      (node (ref "U4") (pin "1") (pinfunction "S1_1") (pintype "passive"))
      (node (ref "U4") (pin "2") (pinfunction "G1_2") (pintype "passive"))
      (node (ref "U4") (pin "3") (pinfunction "S2_3") (pintype "passive"))
    )
    (net (code "48") (name "/S1") (class "Default")
      (node (ref "R62") (pin "2") (pinfunction "2_2") (pintype "passive"))
      (node (ref "U2") (pin "28") (pinfunction "S1_28") (pintype "passive"))
    )
    (net (code "49") (name "/S2") (class "Default")
      (node (ref "R57") (pin "2") (pinfunction "2_2") (pintype "passive"))
      (node (ref "U2") (pin "30") (pinfunction "S2_30") (pintype "passive"))
    )
    (net (code "50") (name "/S3") (class "Default")
      (node (ref "R53") (pin "2") (pinfunction "2_2") (pintype "passive"))
      (node (ref "U2") (pin "33") (pinfunction "S3_33") (pintype "passive"))
    )
    (net (code "51") (name "/S4") (class "Default")
      (node (ref "R50") (pin "2") (pinfunction "2_2") (pintype "passive"))
      (node (ref "U2") (pin "35") (pinfunction "S4_35") (pintype "passive"))
    )
    (net (code "52") (name "/S5") (class "Default")
      (node (ref "R42") (pin "2") (pinfunction "2_2") (pintype "passive"))
      (node (ref "U2") (pin "38") (pinfunction "S5_38") (pintype "passive"))
    )
    (net (code "53") (name "/S6") (class "Default")
      (node (ref "R34") (pin "2") (pinfunction "2_2") (pintype "passive"))
      (node (ref "U2") (pin "40") (pinfunction "S6_40") (pintype "passive"))
    )
    (net (code "54") (name "/S7") (class "Default")
      (node (ref "R30") (pin "2") (pinfunction "2_2") (pintype "passive"))
      (node (ref "U2") (pin "43") (pinfunction "S7_43") (pintype "passive"))
    )
    (net (code "55") (name "/S8") (class "Default")
      (node (ref "R27") (pin "2") (pinfunction "2_2") (pintype "passive"))
      (node (ref "U2") (pin "45") (pinfunction "S8_45") (pintype "passive"))
    )
    (net (code "56") (name "/S9") (class "Default")
      (node (ref "R23") (pin "2") (pinfunction "2_2") (pintype "passive"))
      (node (ref "U2") (pin "48") (pinfunction "S9_48") (pintype "passive"))
    )
    (net (code "57") (name "/S10") (class "Default")
      (node (ref "R20") (pin "2") (pinfunction "2_2") (pintype "passive"))
      (node (ref "U2") (pin "50") (pinfunction "S10_50") (pintype "passive"))
    )
    (net (code "58") (name "/S11") (class "Default")
      (node (ref "R17") (pin "2") (pinfunction "2_2") (pintype "passive"))
      (node (ref "U2") (pin "53") (pinfunction "S11_53") (pintype "passive"))
    )
    (net (code "59") (name "/S12") (class "Default")
      (node (ref "R14") (pin "2") (pinfunction "2_2") (pintype "passive"))
      (node (ref "U2") (pin "55") (pinfunction "S12_55") (pintype "passive"))
    )
    (net (code "60") (name "/S13") (class "Default")
      (node (ref "R11") (pin "2") (pinfunction "2_2") (pintype "passive"))
      (node (ref "U2") (pin "58") (pinfunction "S13_58") (pintype "passive"))
    )
    (net (code "61") (name "/S14") (class "Default")
      (node (ref "R8") (pin "2") (pinfunction "2_2") (pintype "passive"))
      (node (ref "U2") (pin "60") (pinfunction "S14_60") (pintype "passive"))
    )
    (net (code "62") (name "/TEMP_1+") (class "Default")
      (node (ref "R38") (pin "1") (pinfunction "1_1") (pintype "passive"))
      (node (ref "R43") (pin "2") (pinfunction "2_2") (pintype "passive"))
    )
    (net (code "63") (name "/TEMP_2+") (class "Default")
      (node (ref "R39") (pin "1") (pinfunction "1_1") (pintype "passive"))
      (node (ref "R44") (pin "2") (pinfunction "2_2") (pintype "passive"))
    )
    (net (code "64") (name "/TEMP_3+") (class "Default")
      (node (ref "R40") (pin "1") (pinfunction "1_1") (pintype "passive"))
      (node (ref "R45") (pin "2") (pinfunction "2_2") (pintype "passive"))
    )
    (net (code "65") (name "/TEMP_4+") (class "Default")
      (node (ref "R41") (pin "1") (pinfunction "1_1") (pintype "passive"))
      (node (ref "R46") (pin "2") (pinfunction "2_2") (pintype "passive"))
    )
    (net (code "66") (name "/VANA") (class "Default")
      (node (ref "C12") (pin "2") (pinfunction "2_2") (pintype "passive"))
      (node (ref "U2") (pin "21") (pinfunction "VANA_21") (pintype "passive"))
    )
    (net (code "67") (name "/VBAT") (class "Default")
      (node (ref "C15") (pin "2") (pinfunction "2_2") (pintype "passive"))
      (node (ref "C8") (pin "2") (pinfunction "2_2") (pintype "passive"))
      (node (ref "C9") (pin "2") (pinfunction "2_2") (pintype "passive"))
      (node (ref "D1") (pin "K") (pinfunction "K_K") (pintype "passive"))
      (node (ref "Q1") (pin "5") (pinfunction "D_5") (pintype "passive"))
      (node (ref "Q1") (pin "6") (pinfunction "D_6") (pintype "passive"))
      (node (ref "Q1") (pin "7") (pinfunction "D_7") (pintype "passive"))
      (node (ref "Q1") (pin "8") (pinfunction "D_8") (pintype "passive"))
      (node (ref "R5") (pin "2") (pinfunction "2_2") (pintype "passive"))
      (node (ref "U2") (pin "62") (pinfunction "VBAT_62") (pintype "passive"))
    )
    (net (code "68") (name "/VCOM") (class "Default")
      (node (ref "C11") (pin "2") (pinfunction "2_2") (pintype "passive"))
      (node (ref "U2") (pin "20") (pinfunction "SPIEN_20") (pintype "passive"))
      (node (ref "U2") (pin "5") (pinfunction "VCOM_5") (pintype "passive"))
    )
    (net (code "69") (name "/VREG") (class "Default")
      (node (ref "C13") (pin "2") (pinfunction "2_2") (pintype "passive"))
      (node (ref "P2") (pin "1") (pinfunction "1_1") (pintype "passive"))
      (node (ref "Q1") (pin "1") (pinfunction "S_1") (pintype "passive"))
      (node (ref "Q1") (pin "2") (pinfunction "S_2") (pintype "passive"))
      (node (ref "Q1") (pin "3") (pinfunction "S_3") (pintype "passive"))
      (node (ref "U2") (pin "18") (pinfunction "VREG_18") (pintype "passive"))
    )
    (net (code "70") (name "/VTREF") (class "Default")
      (node (ref "C14") (pin "2") (pinfunction "2_2") (pintype "passive"))
      (node (ref "P2") (pin "3") (pinfunction "3_3") (pintype "passive"))
      (node (ref "R38") (pin "2") (pinfunction "2_2") (pintype "passive"))
      (node (ref "R39") (pin "2") (pinfunction "2_2") (pintype "passive"))
      (node (ref "R40") (pin "2") (pinfunction "2_2") (pintype "passive"))
      (node (ref "R41") (pin "2") (pinfunction "2_2") (pintype "passive"))
      (node (ref "U2") (pin "19") (pinfunction "VTREF_19") (pintype "passive"))
    )
    (net (code "71") (name "/aIN_TEMP_1") (class "Default")
      (node (ref "C37") (pin "2") (pinfunction "2_2") (pintype "passive"))
      (node (ref "J1") (pin "5") (pinfunction "5_5") (pintype "passive"))
      (node (ref "R43") (pin "1") (pinfunction "1_1") (pintype "passive"))
      (node (ref "U2") (pin "12") (pinfunction "GPIO3_12") (pintype "passive"))
    )
    (net (code "72") (name "/aIN_TEMP_2") (class "Default")
      (node (ref "C38") (pin "2") (pinfunction "2_2") (pintype "passive"))
      (node (ref "J1") (pin "6") (pinfunction "6_6") (pintype "passive"))
      (node (ref "R44") (pin "1") (pinfunction "1_1") (pintype "passive"))
      (node (ref "U2") (pin "13") (pinfunction "GPIO4_13") (pintype "passive"))
    )
    (net (code "73") (name "/aIN_TEMP_3") (class "Default")
      (node (ref "C39") (pin "2") (pinfunction "2_2") (pintype "passive"))
      (node (ref "J1") (pin "7") (pinfunction "7_7") (pintype "passive"))
      (node (ref "R45") (pin "1") (pinfunction "1_1") (pintype "passive"))
      (node (ref "U2") (pin "14") (pinfunction "GPIO5_14") (pintype "passive"))
    )
    (net (code "74") (name "/aIN_TEMP_4") (class "Default")
      (node (ref "C40") (pin "2") (pinfunction "2_2") (pintype "passive"))
      (node (ref "J1") (pin "8") (pinfunction "8_8") (pintype "passive"))
      (node (ref "R46") (pin "1") (pinfunction "1_1") (pintype "passive"))
      (node (ref "U2") (pin "15") (pinfunction "GPIO6_15") (pintype "passive"))
    )
    (net (code "75") (name "/dIP_SPI_MISO") (class "Default")
      (node (ref "*1") (pin "6") (pinfunction "VOD_6") (pintype "passive"))
    )
    (net (code "76") (name "/dOP_SPI_CLK") (class "Default")
      (node (ref "*1") (pin "4") (pinfunction "VIB_4") (pintype "passive"))
    )
    (net (code "77") (name "/dOP_SPI_CS") (class "Default")
      (node (ref "*1") (pin "3") (pinfunction "VIA_3") (pintype "passive"))
    )
    (net (code "78") (name "/dOP_SPI_MOSI") (class "Default")
      (node (ref "*1") (pin "5") (pinfunction "VIC_5") (pintype "passive"))
    )
    (net (code "79") (name "0V (ISO)") (class "Default")
      (node (ref "*1") (pin "2") (pinfunction "GND1_2") (pintype "passive"))
      (node (ref "*1") (pin "8") (pinfunction "GND1_8") (pintype "passive"))
    )
    (net (code "80") (name "5V (ISO)") (class "Default")
      (node (ref "*1") (pin "1") (pinfunction "VDD1_1") (pintype "passive"))
    )
    (net (code "81") (name "Net-(*1-VID)") (class "Default")
      (node (ref "*1") (pin "11") (pinfunction "VID_11") (pintype "passive"))
      (node (ref "R75") (pin "2") (pinfunction "2_2") (pintype "passive"))
    )
    (net (code "82") (name "Net-(*1-VOA)") (class "Default")
      (node (ref "*1") (pin "14") (pinfunction "VOA_14") (pintype "passive"))
      (node (ref "R72") (pin "2") (pinfunction "2_2") (pintype "passive"))
    )
    (net (code "83") (name "Net-(*1-VOB)") (class "Default")
      (node (ref "*1") (pin "13") (pinfunction "VOB_13") (pintype "passive"))
      (node (ref "R73") (pin "2") (pinfunction "2_2") (pintype "passive"))
    )
    (net (code "84") (name "Net-(*1-VOC)") (class "Default")
      (node (ref "*1") (pin "12") (pinfunction "VOC_12") (pintype "passive"))
      (node (ref "R74") (pin "2") (pinfunction "2_2") (pintype "passive"))
    )
    (net (code "85") (name "Net-(P2-Pad2)") (class "Default")
      (node (ref "P2") (pin "2") (pinfunction "2_2") (pintype "passive"))
      (node (ref "R56") (pin "1") (pinfunction "1_1") (pintype "passive"))
      (node (ref "R58") (pin "2") (pinfunction "2_2") (pintype "passive"))
    )
    (net (code "86") (name "Net-(Q1-G)") (class "Default")
      (node (ref "Q1") (pin "4") (pinfunction "G_4") (pintype "passive"))
      (node (ref "U2") (pin "17") (pinfunction "NPNDRV_17") (pintype "passive"))
    )
    (net (code "87") (name "Net-(R6-Pad2)") (class "Default")
      (node (ref "R6") (pin "2") (pinfunction "2_2") (pintype "passive"))
      (node (ref "R7") (pin "1") (pinfunction "1_1") (pintype "passive"))
      (node (ref "R8") (pin "1") (pinfunction "1_1") (pintype "passive"))
    )
    (net (code "88") (name "Net-(R11-Pad1)") (class "Default")
      (node (ref "R11") (pin "1") (pinfunction "1_1") (pintype "passive"))
      (node (ref "R12") (pin "2") (pinfunction "2_2") (pintype "passive"))
      (node (ref "R13") (pin "1") (pinfunction "1_1") (pintype "passive"))
      (node (ref "R14") (pin "1") (pinfunction "1_1") (pintype "passive"))
    )
    (net (code "89") (name "Net-(R17-Pad1)") (class "Default")
      (node (ref "R17") (pin "1") (pinfunction "1_1") (pintype "passive"))
      (node (ref "R18") (pin "2") (pinfunction "2_2") (pintype "passive"))
      (node (ref "R19") (pin "1") (pinfunction "1_1") (pintype "passive"))
      (node (ref "R20") (pin "1") (pinfunction "1_1") (pintype "passive"))
    )
    (net (code "90") (name "Net-(R23-Pad1)") (class "Default")
      (node (ref "R23") (pin "1") (pinfunction "1_1") (pintype "passive"))
      (node (ref "R24") (pin "2") (pinfunction "2_2") (pintype "passive"))
      (node (ref "R25") (pin "1") (pinfunction "1_1") (pintype "passive"))
      (node (ref "R27") (pin "1") (pinfunction "1_1") (pintype "passive"))
    )
    (net (code "91") (name "Net-(R30-Pad1)") (class "Default")
      (node (ref "R30") (pin "1") (pinfunction "1_1") (pintype "passive"))
      (node (ref "R31") (pin "2") (pinfunction "2_2") (pintype "passive"))
      (node (ref "R33") (pin "1") (pinfunction "1_1") (pintype "passive"))
      (node (ref "R34") (pin "1") (pinfunction "1_1") (pintype "passive"))
    )
    (net (code "92") (name "Net-(R42-Pad1)") (class "Default")
      (node (ref "R42") (pin "1") (pinfunction "1_1") (pintype "passive"))
      (node (ref "R47") (pin "2") (pinfunction "2_2") (pintype "passive"))
      (node (ref "R49") (pin "1") (pinfunction "1_1") (pintype "passive"))
      (node (ref "R50") (pin "1") (pinfunction "1_1") (pintype "passive"))
    )
    (net (code "93") (name "Net-(R53-Pad1)") (class "Default")
      (node (ref "R53") (pin "1") (pinfunction "1_1") (pintype "passive"))
      (node (ref "R54") (pin "2") (pinfunction "2_2") (pintype "passive"))
      (node (ref "R55") (pin "1") (pinfunction "1_1") (pintype "passive"))
      (node (ref "R57") (pin "1") (pinfunction "1_1") (pintype "passive"))
    )
    (net (code "94") (name "Net-(R62-Pad1)") (class "Default")
      (node (ref "R62") (pin "1") (pinfunction "1_1") (pintype "passive"))
      (node (ref "R63") (pin "2") (pinfunction "2_2") (pintype "passive"))
      (node (ref "R64") (pin "1") (pinfunction "1_1") (pintype "passive"))
    )
    (net (code "95") (name "Net-(U2-CAP1)") (class "Default")
      (node (ref "C24") (pin "1") (pinfunction "1_1") (pintype "passive"))
      (node (ref "U2") (pin "64") (pinfunction "CAP1_64") (pintype "passive"))
    )
    (net (code "96") (name "Net-(U2-CAP2)") (class "Default")
      (node (ref "C24") (pin "2") (pinfunction "2_2") (pintype "passive"))
      (node (ref "U2") (pin "63") (pinfunction "CAP2_63") (pintype "passive"))
    )
    (net (code "97") (name "Net-(U2-GPIO1_FAULTH)") (class "Default")
      (node (ref "R37") (pin "1") (pinfunction "1_1") (pintype "passive"))
      (node (ref "U2") (pin "10") (pinfunction "GPIO1_FAULTH_10") (pintype "passive"))
    )
    (net (code "98") (name "Net-(U4-G2)") (class "Default")
      (node (ref "C47") (pin "2") (pinfunction "2_2") (pintype "passive"))
      (node (ref "R56") (pin "2") (pinfunction "2_2") (pintype "passive"))
      (node (ref "U4") (pin "4") (pinfunction "G2_4") (pintype "passive"))
    )
    (net (code "99") (name "unconnected-(*1-RC_OUT-Pad7)") (class "Default")
      (node (ref "*1") (pin "7") (pinfunction "RC_OUT_7") (pintype "passive"))
    )
    (net (code "100") (name "unconnected-(J1-PadP1)") (class "Default")
      (node (ref "J1") (pin "P1") (pinfunction "P1_P1") (pintype "passive"))
    )
    (net (code "101") (name "unconnected-(J1-PadP2)") (class "Default")
      (node (ref "J1") (pin "P2") (pinfunction "P2_P2") (pintype "passive"))
    )
    (net (code "102") (name "unconnected-(U2-GPIO7_WAKEUP-Pad16)") (class "Default")
      (node (ref "U2") (pin "16") (pinfunction "GPIO7_WAKEUP_16") (pintype "passive"))
    )
    (net (code "103") (name "unconnected-(U2-ISOHm-Pad8)") (class "Default")
      (node (ref "U2") (pin "8") (pinfunction "ISOHm_8") (pintype "passive"))
    )
    (net (code "104") (name "unconnected-(U2-ISOHp-Pad7)") (class "Default")
      (node (ref "U2") (pin "7") (pinfunction "ISOHp_7") (pintype "passive"))
    )
  )
)
